# ESP_INPUT_MUX.net
KiCad netlist of a schematic drawn in Altium Designer
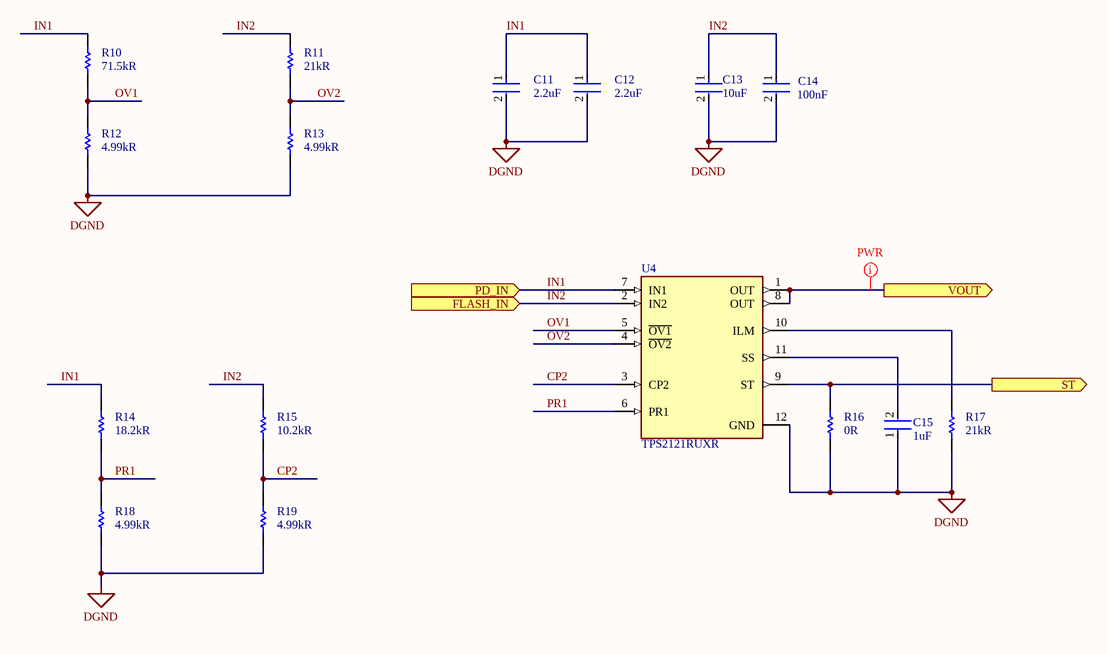
[diagram p0: ESP_INPUT_MUX.SchDoc]

(export (version "E")
  (design (tool "Eeschema 10.0.6"))
  (components
    (comp (ref "C11")
      (value "GRM188R61H225KE11D")
      (footprint "FP-GRM188-0_2-IPC_C")
      (description "Chip Multilayer Ceramic Capacitors for General Purpose, 0603, 2.2uF, X5R, 15%, 10%, 50V")
      (fields (field (name "TOLERANCE") "10%") (field (name "CAPACITANCE") "2.2uF"))
      (libsource (lib "Altium Content Vault") (part "11868f565c42a9108669ba33697ecf6"))
    )
    (comp (ref "C12")
      (value "GRM188R61H225KE11D")
      (footprint "FP-GRM188-0_2-IPC_C")
      (description "Chip Multilayer Ceramic Capacitors for General Purpose, 0603, 2.2uF, X5R, 15%, 10%, 50V")
      (fields (field (name "TOLERANCE") "10%") (field (name "CAPACITANCE") "2.2uF"))
      (libsource (lib "Altium Content Vault") (part "11868f565c42a9108669ba33697ecf6"))
    )
    (comp (ref "C13")
      (value "10uF")
      (footprint "FP-GRM155-0_2-IPC_A")
      (fields (field (name "Comment") "GRM155R61A106ME11D"))
      (libsource (lib "Digital Shovel") (part "b4654b650e69147ec39a6b967a45e02"))
    )
    (comp (ref "C14")
      (value "100nF")
      (footprint "FP-CC0402-IPC_B")
      (fields (field (name "Comment") "CC0402KRX7R9BB104"))
      (libsource (lib "Digital Shovel") (part "11868f565c42a9108669ba33697ecf6"))
    )
    (comp (ref "C15")
      (value "1uF")
      (footprint "FP-0402-L_1_0_0_05-W_0_5-MFG")
      (fields (field (name "MANUFACTURER") "Taiyo Yuden") (field (name "Comment") "EMK105BJ105KV-F"))
      (libsource (lib "Digital Shovel") (part "b4654b650e69147ec39a6b967a45e02"))
    )
    (comp (ref "R10")
      (value "71.5kR")
      (footprint "RESC1005X40X25LL10T10")
      (fields (field (name "MANUFACTURER") "KOA Speer") (field (name "Comment") "RK73H1ETTP7152F"))
      (libsource (lib "Digital Shovel") (part "RES"))
    )
    (comp (ref "R11")
      (value "21kR")
      (footprint "RESC1005X40X25LL10T10")
      (fields (field (name "PART NUMBER") "RK73H1ETTP2102F") (field (name "MANUFACTURER") "KOA Speer"))
      (libsource (lib "Altium Content Vault") (part "RES"))
    )
    (comp (ref "R12")
      (value "4.99kR")
      (footprint "RESC1005X40X25LL10T10")
      (fields (field (name "Comment") "RK73H1ETTP4991F"))
      (libsource (lib "Digital Shovel") (part "RES"))
    )
    (comp (ref "R13")
      (value "4.99kR")
      (footprint "RESC1005X40X25LL10T10")
      (fields (field (name "Comment") "RK73H1ETTP4991F"))
      (libsource (lib "Digital Shovel") (part "RES"))
    )
    (comp (ref "R14")
      (value "18.2kR")
      (footprint "RESC1005X40X25LL10T10")
      (fields (field (name "Comment") "RK73H1ETTP1822F"))
      (libsource (lib "Digital Shovel") (part "RES"))
    )
    (comp (ref "R15")
      (value "10.2kR")
      (footprint "RESC1005X40X25LL10T10")
      (fields (field (name "Comment") "RK73H1ETTP1022F"))
      (libsource (lib "Digital Shovel") (part "RES"))
    )
    (comp (ref "R16")
      (value "0R")
      (footprint "FP-RK73Z1E-IPC_B")
      (description "Metal Glaze/thick Film, 0ohm, Surface Mount, 0402")
      (fields (field (name "Comment") "RK73Z1ETTP"))
      (libsource (lib "Digital Shovel") (part "1029c3af85768c4190bb7ad29bc67b5"))
    )
    (comp (ref "R17")
      (value "21kR")
      (footprint "RESC1005X40X25ML10T10")
      (fields (field (name "PART NUMBER") "RK73H1ETTP2102F") (field (name "MANUFACTURER") "KOA Speer"))
      (libsource (lib "Altium Content Vault") (part "RES"))
    )
    (comp (ref "R18")
      (value "4.99kR")
      (footprint "RESC1005X40X25LL10T10")
      (fields (field (name "Comment") "RK73H1ETTP4991F"))
      (libsource (lib "Digital Shovel") (part "RES"))
    )
    (comp (ref "R19")
      (value "4.99kR")
      (footprint "RESC1005X40X25LL10T10")
      (fields (field (name "Comment") "RK73H1ETTP4991F"))
      (libsource (lib "Digital Shovel") (part "RES"))
    )
    (comp (ref "U4")
      (value "TPS2121RUXR")
      (footprint "FP-RUX0012A-MFG")
      (description "PWR MGMT BATTERY MGMT")
      (fields
        (field (name "MANUFACTURER") "Texas Instruments")
        (field (name "OCTOPART") "https://octopart.com/tps2121ruxr-texas+instruments-95511053")
      )
      (libsource (lib "Altium Content Vault") (part "7e2eec2e55e3eba557c36dfb5d176d9"))
    )
  )
  (nets
    (net (code "1") (name "/CP2") (class "Default")
      (node (ref "R15") (pin "1") (pinfunction "1_1") (pintype "passive"))
      (node (ref "R19") (pin "2") (pinfunction "2_2") (pintype "passive"))
      (node (ref "U4") (pin "3") (pinfunction "CP2_3") (pintype "input"))
    )
    (net (code "2") (name "/IN1") (class "Default")
      (node (ref "C11") (pin "1") (pinfunction "1_1") (pintype "passive"))
      (node (ref "C12") (pin "1") (pinfunction "1_1") (pintype "passive"))
      (node (ref "R10") (pin "2") (pinfunction "2_2") (pintype "passive"))
      (node (ref "R14") (pin "2") (pinfunction "2_2") (pintype "passive"))
      (node (ref "U4") (pin "7") (pinfunction "IN1_7") (pintype "input"))
    )
    (net (code "3") (name "/IN2") (class "Default")
      (node (ref "C13") (pin "1") (pinfunction "1_1") (pintype "passive"))
      (node (ref "C14") (pin "1") (pinfunction "1_1") (pintype "passive"))
      (node (ref "R11") (pin "2") (pinfunction "2_2") (pintype "passive"))
      (node (ref "R15") (pin "2") (pinfunction "2_2") (pintype "passive"))
      (node (ref "U4") (pin "2") (pinfunction "IN2_2") (pintype "input"))
    )
    (net (code "4") (name "/OV1") (class "Default")
      (node (ref "R10") (pin "1") (pinfunction "1_1") (pintype "passive"))
      (node (ref "R12") (pin "2") (pinfunction "2_2") (pintype "passive"))
      (node (ref "U4") (pin "5") (pinfunction "~{OV1}_5") (pintype "input"))
    )
    (net (code "5") (name "/OV2") (class "Default")
      (node (ref "R11") (pin "1") (pinfunction "1_1") (pintype "passive"))
      (node (ref "R13") (pin "2") (pinfunction "2_2") (pintype "passive"))
      (node (ref "U4") (pin "4") (pinfunction "~{OV2}_4") (pintype "input"))
    )
    (net (code "6") (name "/PR1") (class "Default")
      (node (ref "R14") (pin "1") (pinfunction "1_1") (pintype "passive"))
      (node (ref "R18") (pin "2") (pinfunction "2_2") (pintype "passive"))
      (node (ref "U4") (pin "6") (pinfunction "PR1_6") (pintype "input"))
    )
    (net (code "7") (name "/ST") (class "Default")
      (node (ref "R16") (pin "2") (pinfunction "2_2") (pintype "passive"))
      (node (ref "U4") (pin "9") (pinfunction "ST_9") (pintype "output"))
    )
    (net (code "8") (name "/VOUT") (class "Default")
      (node (ref "U4") (pin "1") (pinfunction "OUT_1") (pintype "output"))
      (node (ref "U4") (pin "8") (pinfunction "OUT_8") (pintype "output"))
    )
    (net (code "9") (name "DGND") (class "Default")
      (node (ref "C11") (pin "2") (pinfunction "2_2") (pintype "passive"))
      (node (ref "C12") (pin "2") (pinfunction "2_2") (pintype "passive"))
      (node (ref "C13") (pin "2") (pinfunction "2_2") (pintype "passive"))
      (node (ref "C14") (pin "2") (pinfunction "2_2") (pintype "passive"))
      (node (ref "C15") (pin "1") (pinfunction "1_1") (pintype "passive"))
      (node (ref "R12") (pin "1") (pinfunction "1_1") (pintype "passive"))
      (node (ref "R13") (pin "1") (pinfunction "1_1") (pintype "passive"))
      (node (ref "R16") (pin "1") (pinfunction "1_1") (pintype "passive"))
      (node (ref "R17") (pin "1") (pinfunction "1_1") (pintype "passive"))
      (node (ref "R18") (pin "1") (pinfunction "1_1") (pintype "passive"))
      (node (ref "R19") (pin "1") (pinfunction "1_1") (pintype "passive"))
      (node (ref "U4") (pin "12") (pinfunction "GND_12") (pintype "power_in"))
    )
    (net (code "10") (name "Net-(U4-ILM)") (class "Default")
      (node (ref "R17") (pin "2") (pinfunction "2_2") (pintype "passive"))
      (node (ref "U4") (pin "10") (pinfunction "ILM_10") (pintype "output"))
    )
    (net (code "11") (name "Net-(U4-SS)") (class "Default")
      (node (ref "C15") (pin "2") (pinfunction "2_2") (pintype "passive"))
      (node (ref "U4") (pin "11") (pinfunction "SS_11") (pintype "output"))
    )
  )
)
